# Nixie_Control_Board.net
KiCad netlist of a schematic drawn in EasyEDA
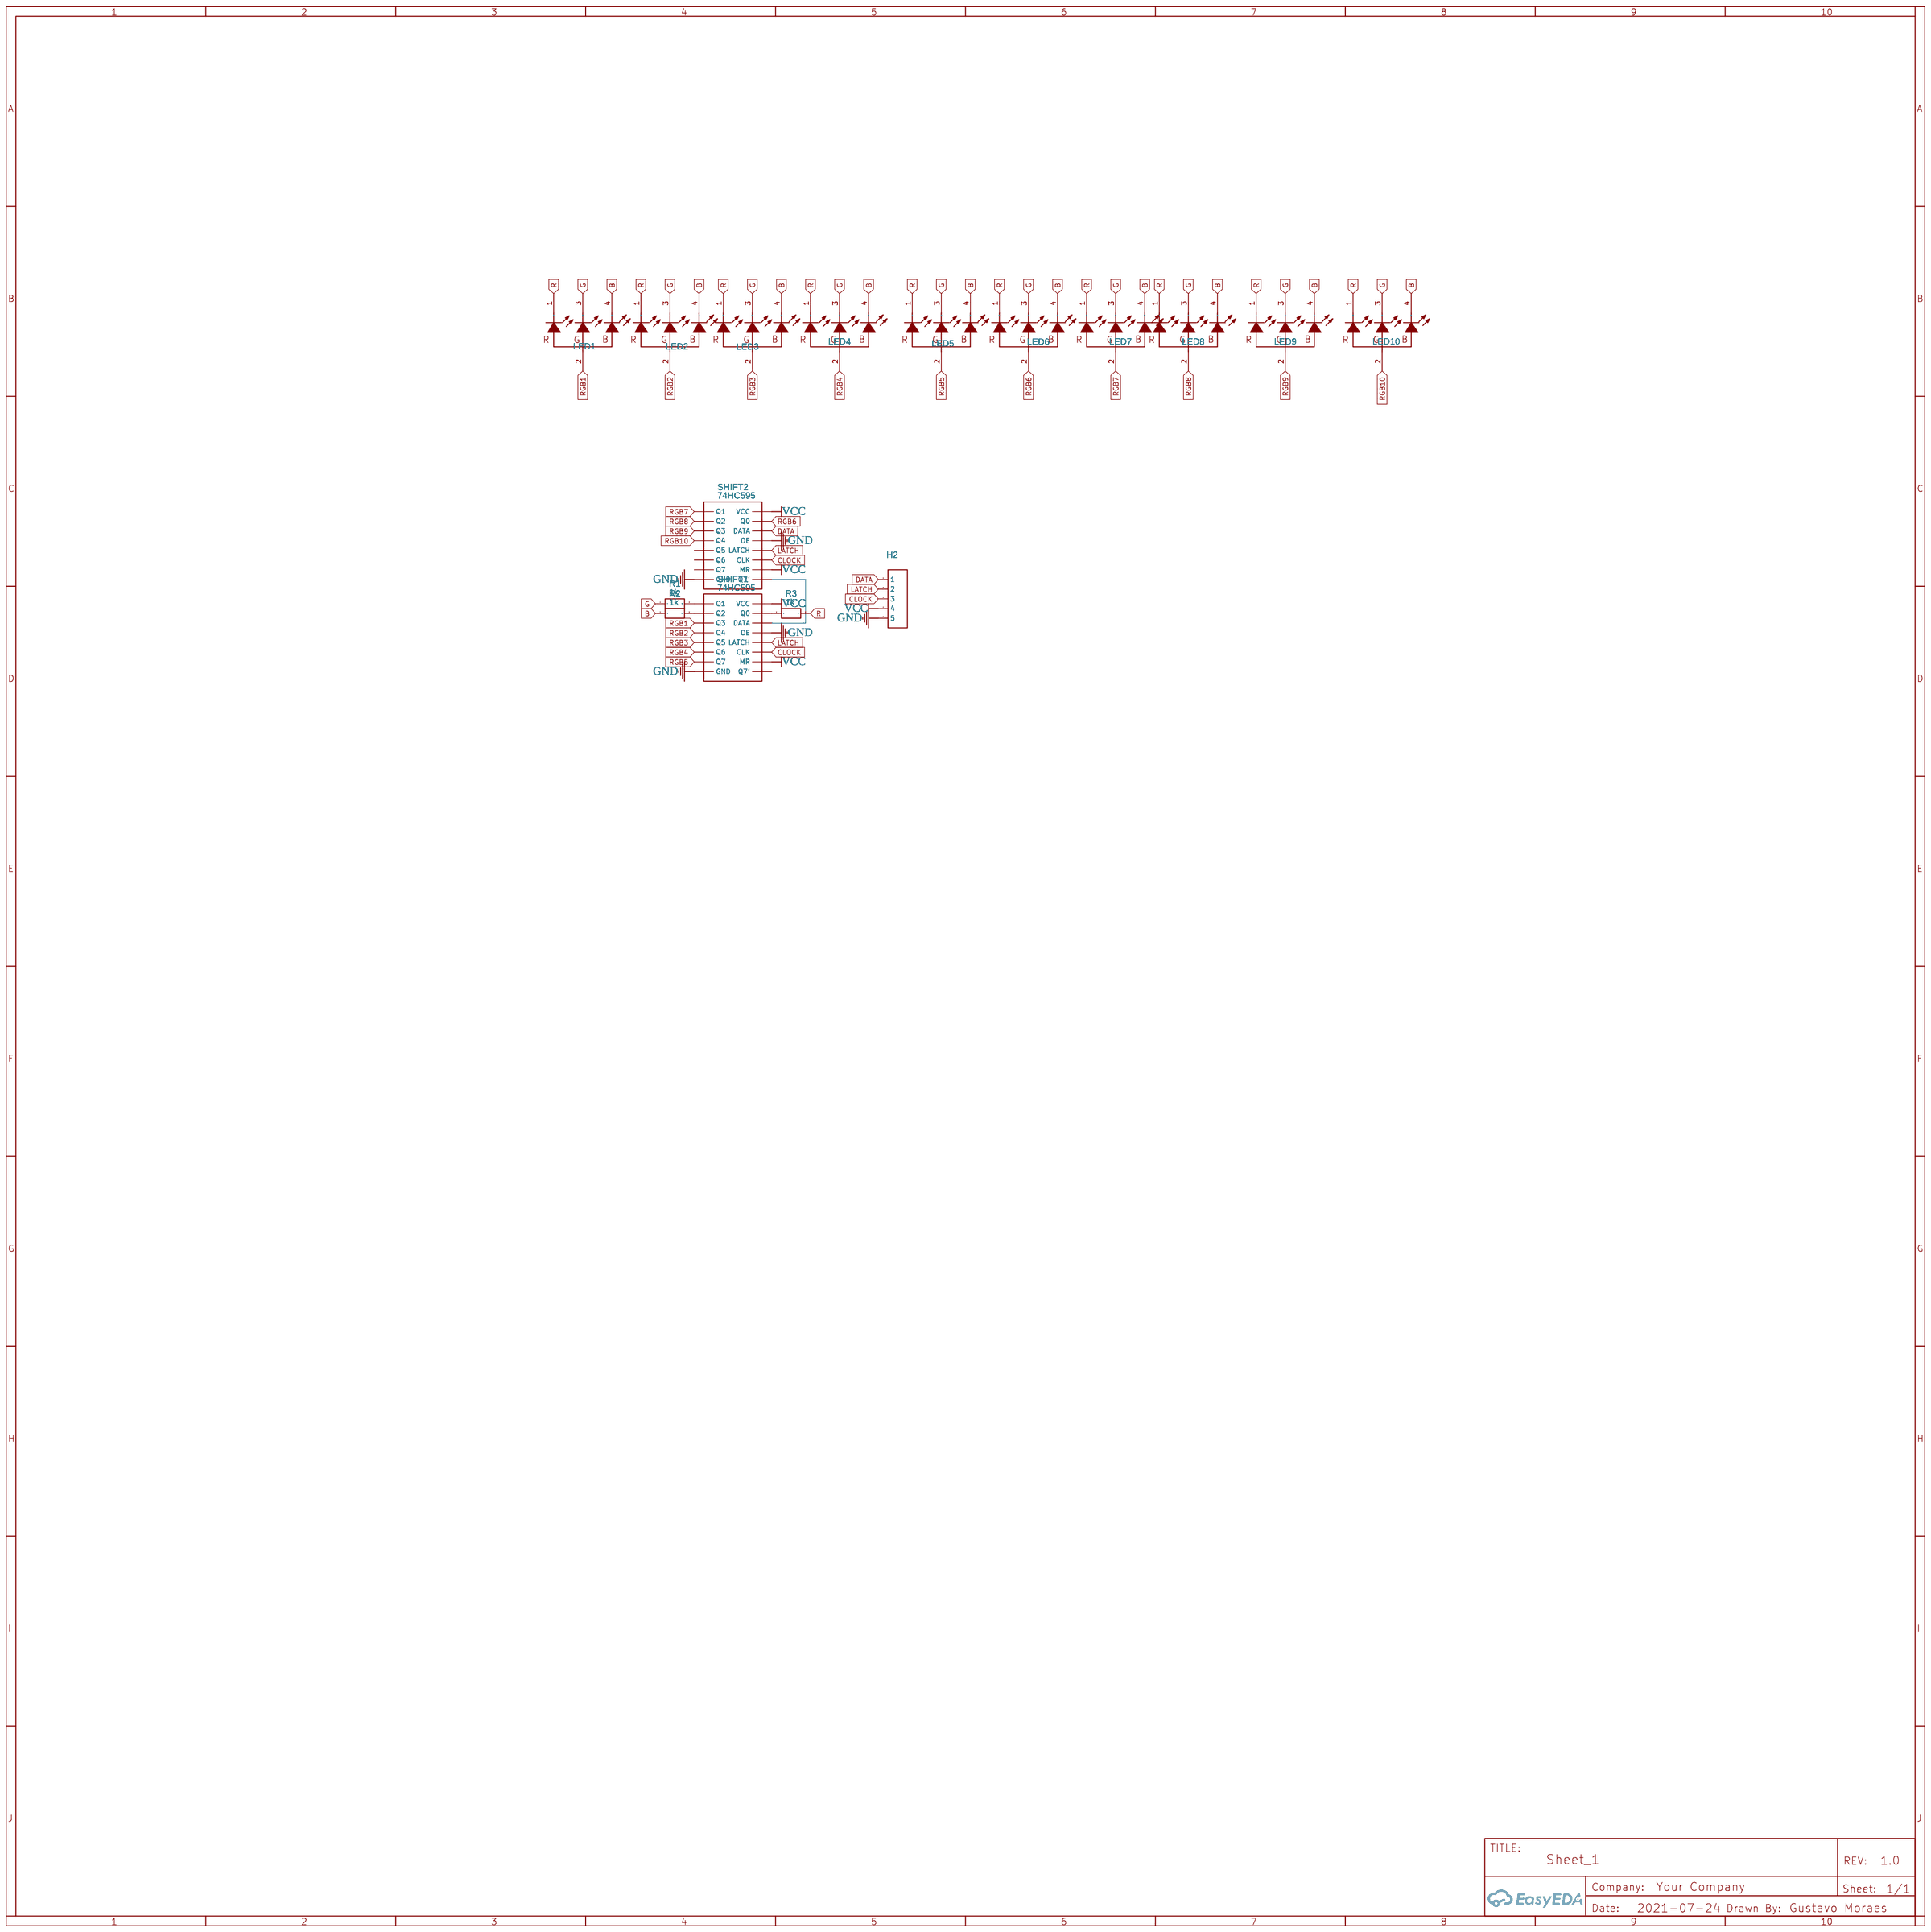
[diagram p0: schematic sheet]

(export (version "E")
  (design (tool "Eeschema 10.0.6"))
  (components
    (comp (ref "H2")
      (value "HDR-F-2.54_1x5")
      (fields (field (name "BOM_Supplier Part") "C50950"))
      (libsource (lib "") (part "HDR-F-2.54_1x5"))
    )
    (comp (ref "LED1")
      (value "φ5 RGB Transparent")
      (fields
        (field (name "BOM_Manufacturer Part") "φ5 RGB Transparent LED")
        (field (name "BOM_Supplier Part") "C32985")
      )
      (libsource (lib "") (part "φ5 RGB Transparent"))
    )
    (comp (ref "LED2")
      (value "φ5 RGB Transparent")
      (fields
        (field (name "BOM_Manufacturer Part") "φ5 RGB Transparent LED")
        (field (name "BOM_Supplier Part") "C32985")
      )
      (libsource (lib "") (part "φ5 RGB Transparent"))
    )
    (comp (ref "LED3")
      (value "φ5 RGB Transparent")
      (fields
        (field (name "BOM_Manufacturer Part") "φ5 RGB Transparent LED")
        (field (name "BOM_Supplier Part") "C32985")
      )
      (libsource (lib "") (part "φ5 RGB Transparent"))
    )
    (comp (ref "LED4")
      (value "φ5 RGB Transparent")
      (fields
        (field (name "BOM_Manufacturer Part") "φ5 RGB Transparent LED")
        (field (name "BOM_Supplier Part") "C32985")
      )
      (libsource (lib "") (part "φ5 RGB Transparent_1"))
    )
    (comp (ref "LED5")
      (value "φ5 RGB Transparent")
      (fields
        (field (name "BOM_Manufacturer Part") "φ5 RGB Transparent LED")
        (field (name "BOM_Supplier Part") "C32985")
      )
      (libsource (lib "") (part "φ5 RGB Transparent"))
    )
    (comp (ref "LED6")
      (value "φ5 RGB Transparent")
      (fields
        (field (name "BOM_Manufacturer Part") "φ5 RGB Transparent LED")
        (field (name "BOM_Supplier Part") "C32985")
      )
      (libsource (lib "") (part "φ5 RGB Transparent"))
    )
    (comp (ref "LED7")
      (value "φ5 RGB Transparent")
      (fields
        (field (name "BOM_Manufacturer Part") "φ5 RGB Transparent LED")
        (field (name "BOM_Supplier Part") "C32985")
      )
      (libsource (lib "") (part "φ5 RGB Transparent"))
    )
    (comp (ref "LED8")
      (value "φ5 RGB Transparent")
      (fields
        (field (name "BOM_Manufacturer Part") "φ5 RGB Transparent LED")
        (field (name "BOM_Supplier Part") "C32985")
      )
      (libsource (lib "") (part "φ5 RGB Transparent"))
    )
    (comp (ref "LED9")
      (value "φ5 RGB Transparent")
      (fields
        (field (name "BOM_Manufacturer Part") "φ5 RGB Transparent LED")
        (field (name "BOM_Supplier Part") "C32985")
      )
      (libsource (lib "") (part "φ5 RGB Transparent"))
    )
    (comp (ref "LED10")
      (value "φ5 RGB Transparent")
      (fields
        (field (name "BOM_Manufacturer Part") "φ5 RGB Transparent LED")
        (field (name "BOM_Supplier Part") "C32985")
      )
      (libsource (lib "") (part "φ5 RGB Transparent"))
    )
    (comp (ref "R1") (value "1k") (libsource (lib "") (part "R_AXIAL-0.3_EU")))
    (comp (ref "R2") (value "1k") (libsource (lib "") (part "R_AXIAL-0.3_EU")))
    (comp (ref "R3") (value "1k") (libsource (lib "") (part "R_AXIAL-0.3_EU")))
    (comp (ref "SHIFT1") (value "74HC595") (libsource (lib "") (part "74HC595")))
    (comp (ref "SHIFT2") (value "74HC595") (libsource (lib "") (part "74HC595")))
  )
  (nets
    (net (code "1") (name "B") (class "Default")
      (node (ref "LED1") (pin "4") (pinfunction "KB_4") (pintype "unspecified"))
      (node (ref "LED10") (pin "4") (pinfunction "KB_4") (pintype "unspecified"))
      (node (ref "LED2") (pin "4") (pinfunction "KB_4") (pintype "unspecified"))
      (node (ref "LED3") (pin "4") (pinfunction "KB_4") (pintype "unspecified"))
      (node (ref "LED4") (pin "4") (pinfunction "KB_4") (pintype "unspecified"))
      (node (ref "LED5") (pin "4") (pinfunction "KB_4") (pintype "unspecified"))
      (node (ref "LED6") (pin "4") (pinfunction "KB_4") (pintype "unspecified"))
      (node (ref "LED7") (pin "4") (pinfunction "KB_4") (pintype "unspecified"))
      (node (ref "LED8") (pin "4") (pinfunction "KB_4") (pintype "unspecified"))
      (node (ref "LED9") (pin "4") (pinfunction "KB_4") (pintype "unspecified"))
      (node (ref "R2") (pin "1") (pinfunction "1_1") (pintype "unspecified"))
    )
    (net (code "2") (name "CLOCK") (class "Default")
      (node (ref "H2") (pin "3") (pinfunction "3_3") (pintype "unspecified"))
      (node (ref "SHIFT1") (pin "11") (pinfunction "CLK_11") (pintype "unspecified"))
      (node (ref "SHIFT2") (pin "11") (pinfunction "CLK_11") (pintype "unspecified"))
    )
    (net (code "3") (name "DATA") (class "Default")
      (node (ref "H2") (pin "1") (pinfunction "1_1") (pintype "unspecified"))
      (node (ref "SHIFT2") (pin "14") (pinfunction "DATA_14") (pintype "unspecified"))
    )
    (net (code "4") (name "G") (class "Default")
      (node (ref "LED1") (pin "3") (pinfunction "KG_3") (pintype "unspecified"))
      (node (ref "LED10") (pin "3") (pinfunction "KG_3") (pintype "unspecified"))
      (node (ref "LED2") (pin "3") (pinfunction "KG_3") (pintype "unspecified"))
      (node (ref "LED3") (pin "3") (pinfunction "KG_3") (pintype "unspecified"))
      (node (ref "LED4") (pin "3") (pinfunction "KG_3") (pintype "unspecified"))
      (node (ref "LED5") (pin "3") (pinfunction "KG_3") (pintype "unspecified"))
      (node (ref "LED6") (pin "3") (pinfunction "KG_3") (pintype "unspecified"))
      (node (ref "LED7") (pin "3") (pinfunction "KG_3") (pintype "unspecified"))
      (node (ref "LED8") (pin "3") (pinfunction "KG_3") (pintype "unspecified"))
      (node (ref "LED9") (pin "3") (pinfunction "KG_3") (pintype "unspecified"))
      (node (ref "R1") (pin "1") (pinfunction "1_1") (pintype "unspecified"))
    )
    (net (code "5") (name "GND") (class "Default")
      (node (ref "H2") (pin "5") (pinfunction "5_5") (pintype "unspecified"))
      (node (ref "SHIFT1") (pin "13") (pinfunction "OE_13") (pintype "unspecified"))
      (node (ref "SHIFT1") (pin "8") (pinfunction "GND_8") (pintype "unspecified"))
      (node (ref "SHIFT2") (pin "13") (pinfunction "OE_13") (pintype "unspecified"))
      (node (ref "SHIFT2") (pin "8") (pinfunction "GND_8") (pintype "unspecified"))
    )
    (net (code "6") (name "LATCH") (class "Default")
      (node (ref "H2") (pin "2") (pinfunction "2_2") (pintype "unspecified"))
      (node (ref "SHIFT1") (pin "12") (pinfunction "LATCH_12") (pintype "unspecified"))
      (node (ref "SHIFT2") (pin "12") (pinfunction "LATCH_12") (pintype "unspecified"))
    )
    (net (code "7") (name "Net-(SHIFT1-DATA)") (class "Default")
      (node (ref "SHIFT1") (pin "14") (pinfunction "DATA_14") (pintype "unspecified"))
      (node (ref "SHIFT2") (pin "9") (pinfunction "Q7'_9") (pintype "unspecified"))
    )
    (net (code "8") (name "Net-(SHIFT1-Q0)") (class "Default")
      (node (ref "R3") (pin "1") (pinfunction "1_1") (pintype "unspecified"))
      (node (ref "SHIFT1") (pin "15") (pinfunction "Q0_15") (pintype "unspecified"))
    )
    (net (code "9") (name "Net-(SHIFT1-Q1)") (class "Default")
      (node (ref "R1") (pin "2") (pinfunction "2_2") (pintype "unspecified"))
      (node (ref "SHIFT1") (pin "1") (pinfunction "Q1_1") (pintype "unspecified"))
    )
    (net (code "10") (name "Net-(SHIFT1-Q2)") (class "Default")
      (node (ref "R2") (pin "2") (pinfunction "2_2") (pintype "unspecified"))
      (node (ref "SHIFT1") (pin "2") (pinfunction "Q2_2") (pintype "unspecified"))
    )
    (net (code "11") (name "R") (class "Default")
      (node (ref "LED1") (pin "1") (pinfunction "KR_1") (pintype "unspecified"))
      (node (ref "LED10") (pin "1") (pinfunction "KR_1") (pintype "unspecified"))
      (node (ref "LED2") (pin "1") (pinfunction "KR_1") (pintype "unspecified"))
      (node (ref "LED3") (pin "1") (pinfunction "KR_1") (pintype "unspecified"))
      (node (ref "LED4") (pin "1") (pinfunction "KR_1") (pintype "unspecified"))
      (node (ref "LED5") (pin "1") (pinfunction "KR_1") (pintype "unspecified"))
      (node (ref "LED6") (pin "1") (pinfunction "KR_1") (pintype "unspecified"))
      (node (ref "LED7") (pin "1") (pinfunction "KR_1") (pintype "unspecified"))
      (node (ref "LED8") (pin "1") (pinfunction "KR_1") (pintype "unspecified"))
      (node (ref "LED9") (pin "1") (pinfunction "KR_1") (pintype "unspecified"))
      (node (ref "R3") (pin "2") (pinfunction "2_2") (pintype "unspecified"))
    )
    (net (code "12") (name "RGB1") (class "Default")
      (node (ref "LED1") (pin "2") (pinfunction "CA_2") (pintype "unspecified"))
      (node (ref "SHIFT1") (pin "3") (pinfunction "Q3_3") (pintype "unspecified"))
    )
    (net (code "13") (name "RGB2") (class "Default")
      (node (ref "LED2") (pin "2") (pinfunction "CA_2") (pintype "unspecified"))
      (node (ref "SHIFT1") (pin "4") (pinfunction "Q4_4") (pintype "unspecified"))
    )
    (net (code "14") (name "RGB3") (class "Default")
      (node (ref "LED3") (pin "2") (pinfunction "CA_2") (pintype "unspecified"))
      (node (ref "SHIFT1") (pin "5") (pinfunction "Q5_5") (pintype "unspecified"))
    )
    (net (code "15") (name "RGB4") (class "Default")
      (node (ref "LED4") (pin "2") (pinfunction "CA_2") (pintype "unspecified"))
      (node (ref "SHIFT1") (pin "6") (pinfunction "Q6_6") (pintype "unspecified"))
    )
    (net (code "16") (name "RGB5") (class "Default")
      (node (ref "LED5") (pin "2") (pinfunction "CA_2") (pintype "unspecified"))
      (node (ref "SHIFT1") (pin "7") (pinfunction "Q7_7") (pintype "unspecified"))
    )
    (net (code "17") (name "RGB6") (class "Default")
      (node (ref "LED6") (pin "2") (pinfunction "CA_2") (pintype "unspecified"))
      (node (ref "SHIFT2") (pin "15") (pinfunction "Q0_15") (pintype "unspecified"))
    )
    (net (code "18") (name "RGB7") (class "Default")
      (node (ref "LED7") (pin "2") (pinfunction "CA_2") (pintype "unspecified"))
      (node (ref "SHIFT2") (pin "1") (pinfunction "Q1_1") (pintype "unspecified"))
    )
    (net (code "19") (name "RGB8") (class "Default")
      (node (ref "LED8") (pin "2") (pinfunction "CA_2") (pintype "unspecified"))
      (node (ref "SHIFT2") (pin "2") (pinfunction "Q2_2") (pintype "unspecified"))
    )
    (net (code "20") (name "RGB9") (class "Default")
      (node (ref "LED9") (pin "2") (pinfunction "CA_2") (pintype "unspecified"))
      (node (ref "SHIFT2") (pin "3") (pinfunction "Q3_3") (pintype "unspecified"))
    )
    (net (code "21") (name "RGB10") (class "Default")
      (node (ref "LED10") (pin "2") (pinfunction "CA_2") (pintype "unspecified"))
      (node (ref "SHIFT2") (pin "4") (pinfunction "Q4_4") (pintype "unspecified"))
    )
    (net (code "22") (name "VCC") (class "Default")
      (node (ref "H2") (pin "4") (pinfunction "4_4") (pintype "unspecified"))
      (node (ref "SHIFT1") (pin "10") (pinfunction "MR_10") (pintype "unspecified"))
      (node (ref "SHIFT1") (pin "16") (pinfunction "VCC_16") (pintype "unspecified"))
      (node (ref "SHIFT2") (pin "10") (pinfunction "MR_10") (pintype "unspecified"))
      (node (ref "SHIFT2") (pin "16") (pinfunction "VCC_16") (pintype "unspecified"))
    )
    (net (code "23") (name "unconnected-(SHIFT1-Q7'-Pad9)") (class "Default")
      (node (ref "SHIFT1") (pin "9") (pinfunction "Q7'_9") (pintype "unspecified"))
    )
    (net (code "24") (name "unconnected-(SHIFT2-Q5-Pad5)") (class "Default")
      (node (ref "SHIFT2") (pin "5") (pinfunction "Q5_5") (pintype "unspecified"))
    )
    (net (code "25") (name "unconnected-(SHIFT2-Q6-Pad6)") (class "Default")
      (node (ref "SHIFT2") (pin "6") (pinfunction "Q6_6") (pintype "unspecified"))
    )
    (net (code "26") (name "unconnected-(SHIFT2-Q7-Pad7)") (class "Default")
      (node (ref "SHIFT2") (pin "7") (pinfunction "Q7_7") (pintype "unspecified"))
    )
  )
)
